# atmega16_generalpurpose_board.net
KiCad netlist of a schematic drawn in EAGLE
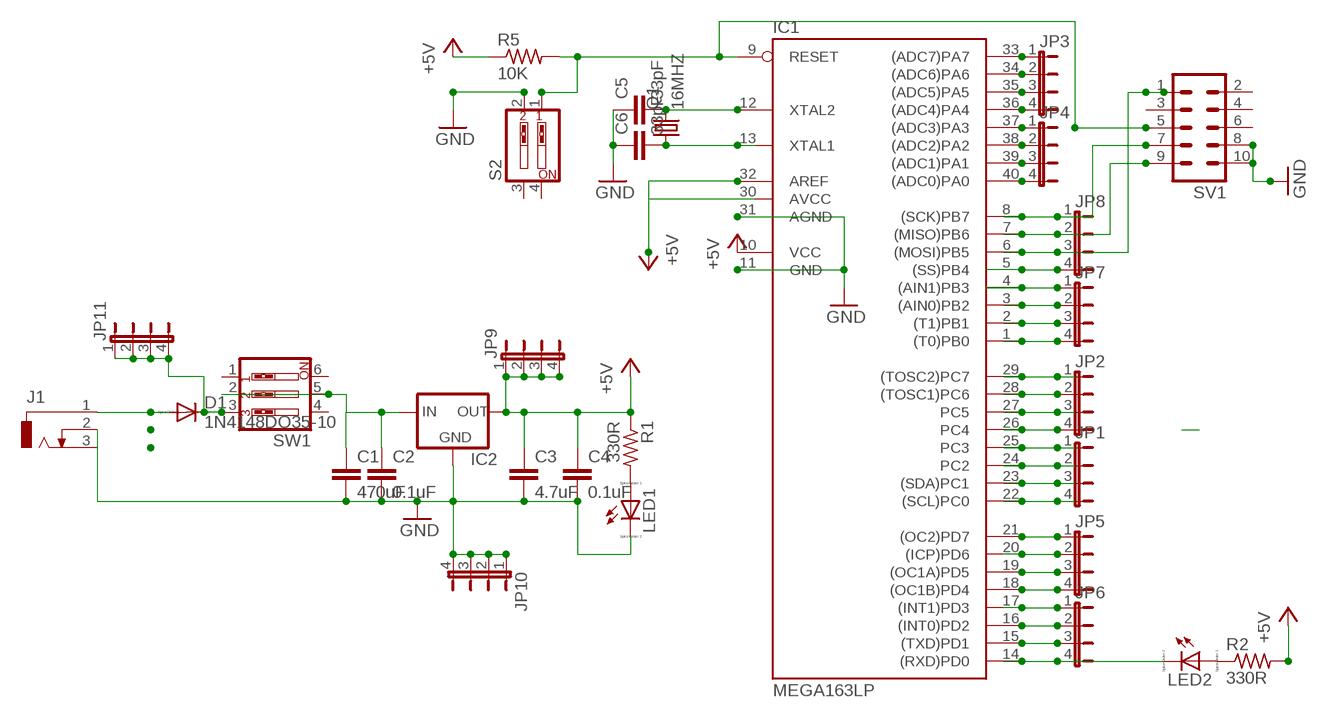
[diagram p0: schematic, sheet 1]

(export (version "E")
  (design (tool "Eeschema 10.0.6"))
  (components
    (comp (ref "C1")
      (value "470uF")
      (footprint "eagle-import:C2.5-4")
      (libsource (lib "eagle-import") (part "C2.5/4"))
    )
    (comp (ref "C2")
      (value "0.1uF")
      (footprint "eagle-import:C2.5-4")
      (libsource (lib "eagle-import") (part "C2.5/4"))
    )
    (comp (ref "C3")
      (value "4.7uF")
      (footprint "eagle-import:C2.5-4")
      (libsource (lib "eagle-import") (part "C2.5/4"))
    )
    (comp (ref "C4")
      (value "0.1uF")
      (footprint "eagle-import:C2.5-4")
      (libsource (lib "eagle-import") (part "C2.5/4"))
    )
    (comp (ref "C5")
      (value "33pF")
      (footprint "eagle-import:C2.5-4")
      (libsource (lib "eagle-import") (part "C2.5/4"))
    )
    (comp (ref "C6")
      (value "33pF")
      (footprint "eagle-import:C2.5-4")
      (libsource (lib "eagle-import") (part "C2.5/4"))
    )
    (comp (ref "D1")
      (value "1N4148DO35-10")
      (footprint "eagle-import:DO35-10")
      (libsource (lib "eagle-import") (part "1N4148DO35-10"))
    )
    (comp (ref "IC1")
      (value "MEGA163LP")
      (footprint "eagle-import:DIL40")
      (libsource (lib "eagle-import") (part "MEGA163PL"))
    )
    (comp (ref "IC2")
      (value "78XXS")
      (footprint "eagle-import:78XXS")
      (libsource (lib "eagle-import") (part "78XXS"))
    )
    (comp (ref "J1")
      (value "DCJ0303")
      (footprint "eagle-import:DCJ0303")
      (libsource (lib "eagle-import") (part "DCJ0303"))
    )
    (comp (ref "JP1")
      (value "JP4E")
      (footprint "eagle-import:JP4")
      (libsource (lib "eagle-import") (part "JP4E"))
    )
    (comp (ref "JP2")
      (value "JP4E")
      (footprint "eagle-import:JP4")
      (libsource (lib "eagle-import") (part "JP4E"))
    )
    (comp (ref "JP3")
      (value "JP4E")
      (footprint "eagle-import:JP4")
      (libsource (lib "eagle-import") (part "JP4E"))
    )
    (comp (ref "JP4")
      (value "JP4E")
      (footprint "eagle-import:JP4")
      (libsource (lib "eagle-import") (part "JP4E"))
    )
    (comp (ref "JP5")
      (value "JP4E")
      (footprint "eagle-import:JP4")
      (libsource (lib "eagle-import") (part "JP4E"))
    )
    (comp (ref "JP6")
      (value "JP4E")
      (footprint "eagle-import:JP4")
      (libsource (lib "eagle-import") (part "JP4E"))
    )
    (comp (ref "JP7")
      (value "JP4E")
      (footprint "eagle-import:JP4")
      (libsource (lib "eagle-import") (part "JP4E"))
    )
    (comp (ref "JP8")
      (value "JP4E")
      (footprint "eagle-import:JP4")
      (libsource (lib "eagle-import") (part "JP4E"))
    )
    (comp (ref "JP9")
      (value "JP4E")
      (footprint "eagle-import:JP4")
      (libsource (lib "eagle-import") (part "JP4E"))
    )
    (comp (ref "JP10")
      (value "JP4E")
      (footprint "eagle-import:JP4")
      (libsource (lib "eagle-import") (part "JP4E"))
    )
    (comp (ref "JP11")
      (value "JP4E")
      (footprint "eagle-import:JP4")
      (libsource (lib "eagle-import") (part "JP4E"))
    )
    (comp (ref "LED1")
      (value "LED_ELD260")
      (footprint "eagle-import:LED_LD260")
      (libsource (lib "eagle-import") (part "LED_ELD260"))
    )
    (comp (ref "LED2")
      (value "LED_ELD260")
      (footprint "eagle-import:LED_LD260")
      (libsource (lib "eagle-import") (part "LED_ELD260"))
    )
    (comp (ref "Q1")
      (value "16MHZ")
      (footprint "eagle-import:HC49U-V")
      (libsource (lib "eagle-import") (part "CRYSTALHC49U-V"))
    )
    (comp (ref "R1")
      (value "330R")
      (footprint "eagle-import:0204_7")
      (libsource (lib "eagle-import") (part "R-US_0204/7"))
    )
    (comp (ref "R2")
      (value "330R")
      (footprint "eagle-import:0204_7")
      (libsource (lib "eagle-import") (part "R-US_0204/7"))
    )
    (comp (ref "R5")
      (value "10K")
      (footprint "eagle-import:0204_7")
      (libsource (lib "eagle-import") (part "R-US_0204/7"))
    )
    (comp (ref "S2")
      (value "SW_DIP-2")
      (footprint "eagle-import:EDG-02")
      (libsource (lib "eagle-import") (part "SW_DIP-2"))
    )
    (comp (ref "SV1")
      (value "MA05-2")
      (footprint "eagle-import:MA05-2")
      (libsource (lib "eagle-import") (part "MA05-2"))
    )
    (comp (ref "SW1")
      (value "SW_DIP-3")
      (footprint "eagle-import:EDG-03")
      (libsource (lib "eagle-import") (part "SW_DIP-3"))
    )
  )
  (nets
    (net (code "1") (name "+5V") (class "Default")
      (node (ref "C3") (pin "1") (pinfunction "1_1") (pintype "passive"))
      (node (ref "C4") (pin "1") (pinfunction "1_1") (pintype "passive"))
      (node (ref "IC1") (pin "10") (pinfunction "VCC_10") (pintype "power_in"))
      (node (ref "IC1") (pin "32") (pinfunction "AREF_32") (pintype "passive"))
      (node (ref "IC2") (pin "OUT") (pinfunction "OUT_OUT") (pintype "passive"))
      (node (ref "JP9") (pin "1") (pinfunction "1_1") (pintype "passive"))
      (node (ref "JP9") (pin "2") (pinfunction "2_2") (pintype "passive"))
      (node (ref "JP9") (pin "3") (pinfunction "3_3") (pintype "passive"))
      (node (ref "JP9") (pin "4") (pinfunction "4_4") (pintype "passive"))
      (node (ref "R1") (pin "1") (pinfunction "1_1") (pintype "passive"))
      (node (ref "R2") (pin "2") (pinfunction "2_2") (pintype "passive"))
      (node (ref "R5") (pin "1") (pinfunction "1_1") (pintype "passive"))
    )
    (net (code "2") (name "/AVCC") (class "Default")
      (node (ref "IC1") (pin "30") (pinfunction "AVCC_30") (pintype "power_in"))
    )
    (net (code "3") (name "/N$18") (class "Default")
      (node (ref "IC1") (pin "27") (pinfunction "PC5_27") (pintype "bidirectional"))
      (node (ref "JP2") (pin "3") (pinfunction "3_3") (pintype "passive"))
    )
    (net (code "4") (name "GND") (class "Default")
      (node (ref "C1") (pin "2") (pinfunction "2_2") (pintype "passive"))
      (node (ref "C2") (pin "2") (pinfunction "2_2") (pintype "passive"))
      (node (ref "C3") (pin "2") (pinfunction "2_2") (pintype "passive"))
      (node (ref "C4") (pin "2") (pinfunction "2_2") (pintype "passive"))
      (node (ref "C5") (pin "1") (pinfunction "1_1") (pintype "passive"))
      (node (ref "C6") (pin "1") (pinfunction "1_1") (pintype "passive"))
      (node (ref "IC1") (pin "11") (pinfunction "GND_11") (pintype "power_in"))
      (node (ref "IC1") (pin "31") (pinfunction "AGND_31") (pintype "power_in"))
      (node (ref "IC2") (pin "GND") (pinfunction "GND_GND") (pintype "input"))
      (node (ref "J1") (pin "2") (pinfunction "2_2") (pintype "passive"))
      (node (ref "J1") (pin "3") (pinfunction "3_3") (pintype "passive"))
      (node (ref "JP10") (pin "1") (pinfunction "1_1") (pintype "passive"))
      (node (ref "JP10") (pin "2") (pinfunction "2_2") (pintype "passive"))
      (node (ref "JP10") (pin "3") (pinfunction "3_3") (pintype "passive"))
      (node (ref "JP10") (pin "4") (pinfunction "4_4") (pintype "passive"))
      (node (ref "LED1") (pin "K") (pinfunction "C_K") (pintype "passive"))
      (node (ref "S2") (pin "2") (pinfunction "2_2") (pintype "passive"))
      (node (ref "SV1") (pin "10") (pinfunction "10_10") (pintype "passive"))
      (node (ref "SV1") (pin "8") (pinfunction "8_8") (pintype "passive"))
    )
    (net (code "5") (name "Net-(C1-Pad1)") (class "Default")
      (node (ref "C1") (pin "1") (pinfunction "1_1") (pintype "passive"))
      (node (ref "C2") (pin "1") (pinfunction "1_1") (pintype "passive"))
      (node (ref "IC2") (pin "IN") (pinfunction "IN_IN") (pintype "input"))
      (node (ref "SW1") (pin "2") (pinfunction "2_2") (pintype "passive"))
      (node (ref "SW1") (pin "5") (pinfunction "5_5") (pintype "passive"))
    )
    (net (code "6") (name "Net-(D1-PadA)") (class "Default")
      (node (ref "D1") (pin "A") (pinfunction "A_A") (pintype "passive"))
      (node (ref "J1") (pin "1") (pinfunction "1_1") (pintype "passive"))
    )
    (net (code "7") (name "Net-(D1-PadC)") (class "Default")
      (node (ref "D1") (pin "C") (pinfunction "C_C") (pintype "passive"))
      (node (ref "JP11") (pin "1") (pinfunction "1_1") (pintype "passive"))
      (node (ref "JP11") (pin "2") (pinfunction "2_2") (pintype "passive"))
      (node (ref "JP11") (pin "3") (pinfunction "3_3") (pintype "passive"))
      (node (ref "JP11") (pin "4") (pinfunction "4_4") (pintype "passive"))
      (node (ref "SW1") (pin "3") (pinfunction "3_3") (pintype "passive"))
    )
    (net (code "8") (name "Net-(IC1-(ADC0)PA0)") (class "Default")
      (node (ref "IC1") (pin "40") (pinfunction "(ADC0)PA0_40") (pintype "bidirectional"))
      (node (ref "JP4") (pin "4") (pinfunction "4_4") (pintype "passive"))
    )
    (net (code "9") (name "Net-(IC1-(ADC1)PA1)") (class "Default")
      (node (ref "IC1") (pin "39") (pinfunction "(ADC1)PA1_39") (pintype "bidirectional"))
      (node (ref "JP4") (pin "3") (pinfunction "3_3") (pintype "passive"))
    )
    (net (code "10") (name "Net-(IC1-(ADC2)PA2)") (class "Default")
      (node (ref "IC1") (pin "38") (pinfunction "(ADC2)PA2_38") (pintype "bidirectional"))
      (node (ref "JP4") (pin "2") (pinfunction "2_2") (pintype "passive"))
    )
    (net (code "11") (name "Net-(IC1-(ADC3)PA3)") (class "Default")
      (node (ref "IC1") (pin "37") (pinfunction "(ADC3)PA3_37") (pintype "bidirectional"))
      (node (ref "JP4") (pin "1") (pinfunction "1_1") (pintype "passive"))
    )
    (net (code "12") (name "Net-(IC1-(ADC4)PA4)") (class "Default")
      (node (ref "IC1") (pin "36") (pinfunction "(ADC4)PA4_36") (pintype "bidirectional"))
      (node (ref "JP3") (pin "4") (pinfunction "4_4") (pintype "passive"))
    )
    (net (code "13") (name "Net-(IC1-(ADC5)PA5)") (class "Default")
      (node (ref "IC1") (pin "35") (pinfunction "(ADC5)PA5_35") (pintype "bidirectional"))
      (node (ref "JP3") (pin "3") (pinfunction "3_3") (pintype "passive"))
    )
    (net (code "14") (name "Net-(IC1-(ADC6)PA6)") (class "Default")
      (node (ref "IC1") (pin "34") (pinfunction "(ADC6)PA6_34") (pintype "bidirectional"))
      (node (ref "JP3") (pin "2") (pinfunction "2_2") (pintype "passive"))
    )
    (net (code "15") (name "Net-(IC1-(ADC7)PA7)") (class "Default")
      (node (ref "IC1") (pin "33") (pinfunction "(ADC7)PA7_33") (pintype "bidirectional"))
      (node (ref "JP3") (pin "1") (pinfunction "1_1") (pintype "passive"))
    )
    (net (code "16") (name "Net-(IC1-(AIN0)PB2)") (class "Default")
      (node (ref "IC1") (pin "3") (pinfunction "(AIN0)PB2_3") (pintype "bidirectional"))
      (node (ref "JP7") (pin "2") (pinfunction "2_2") (pintype "passive"))
    )
    (net (code "17") (name "Net-(IC1-(AIN1)PB3)") (class "Default")
      (node (ref "IC1") (pin "4") (pinfunction "(AIN1)PB3_4") (pintype "bidirectional"))
      (node (ref "JP7") (pin "1") (pinfunction "1_1") (pintype "passive"))
    )
    (net (code "18") (name "Net-(IC1-(ICP)PD6)") (class "Default")
      (node (ref "IC1") (pin "20") (pinfunction "(ICP)PD6_20") (pintype "bidirectional"))
      (node (ref "JP5") (pin "2") (pinfunction "2_2") (pintype "passive"))
    )
    (net (code "19") (name "Net-(IC1-(INT0)PD2)") (class "Default")
      (node (ref "IC1") (pin "16") (pinfunction "(INT0)PD2_16") (pintype "bidirectional"))
      (node (ref "JP6") (pin "2") (pinfunction "2_2") (pintype "passive"))
    )
    (net (code "20") (name "Net-(IC1-(INT1)PD3)") (class "Default")
      (node (ref "IC1") (pin "17") (pinfunction "(INT1)PD3_17") (pintype "bidirectional"))
      (node (ref "JP6") (pin "1") (pinfunction "1_1") (pintype "passive"))
    )
    (net (code "21") (name "Net-(IC1-(MISO)PB6)") (class "Default")
      (node (ref "IC1") (pin "7") (pinfunction "(MISO)PB6_7") (pintype "bidirectional"))
      (node (ref "JP8") (pin "2") (pinfunction "2_2") (pintype "passive"))
      (node (ref "SV1") (pin "9") (pinfunction "9_9") (pintype "passive"))
    )
    (net (code "22") (name "Net-(IC1-(MOSI)PB5)") (class "Default")
      (node (ref "IC1") (pin "6") (pinfunction "(MOSI)PB5_6") (pintype "bidirectional"))
      (node (ref "JP8") (pin "3") (pinfunction "3_3") (pintype "passive"))
      (node (ref "SV1") (pin "1") (pinfunction "1_1") (pintype "passive"))
    )
    (net (code "23") (name "Net-(IC1-(OC1A)PD5)") (class "Default")
      (node (ref "IC1") (pin "19") (pinfunction "(OC1A)PD5_19") (pintype "bidirectional"))
      (node (ref "JP5") (pin "3") (pinfunction "3_3") (pintype "passive"))
    )
    (net (code "24") (name "Net-(IC1-(OC1B)PD4)") (class "Default")
      (node (ref "IC1") (pin "18") (pinfunction "(OC1B)PD4_18") (pintype "bidirectional"))
      (node (ref "JP5") (pin "4") (pinfunction "4_4") (pintype "passive"))
    )
    (net (code "25") (name "Net-(IC1-(OC2)PD7)") (class "Default")
      (node (ref "IC1") (pin "21") (pinfunction "(OC2)PD7_21") (pintype "bidirectional"))
      (node (ref "JP5") (pin "1") (pinfunction "1_1") (pintype "passive"))
    )
    (net (code "26") (name "Net-(IC1-(RXD)PD0)") (class "Default")
      (node (ref "IC1") (pin "14") (pinfunction "(RXD)PD0_14") (pintype "bidirectional"))
      (node (ref "JP6") (pin "4") (pinfunction "4_4") (pintype "passive"))
      (node (ref "LED2") (pin "K") (pinfunction "C_K") (pintype "passive"))
    )
    (net (code "27") (name "Net-(IC1-(SCK)PB7)") (class "Default")
      (node (ref "IC1") (pin "8") (pinfunction "(SCK)PB7_8") (pintype "bidirectional"))
      (node (ref "JP8") (pin "1") (pinfunction "1_1") (pintype "passive"))
      (node (ref "SV1") (pin "7") (pinfunction "7_7") (pintype "passive"))
    )
    (net (code "28") (name "Net-(IC1-(SCL)PC0)") (class "Default")
      (node (ref "IC1") (pin "22") (pinfunction "(SCL)PC0_22") (pintype "bidirectional"))
      (node (ref "JP1") (pin "4") (pinfunction "4_4") (pintype "passive"))
    )
    (net (code "29") (name "Net-(IC1-(SDA)PC1)") (class "Default")
      (node (ref "IC1") (pin "23") (pinfunction "(SDA)PC1_23") (pintype "bidirectional"))
      (node (ref "JP1") (pin "3") (pinfunction "3_3") (pintype "passive"))
    )
    (net (code "30") (name "Net-(IC1-(SS)PB4)") (class "Default")
      (node (ref "IC1") (pin "5") (pinfunction "(SS)PB4_5") (pintype "bidirectional"))
      (node (ref "JP8") (pin "4") (pinfunction "4_4") (pintype "passive"))
    )
    (net (code "31") (name "Net-(IC1-(T0)PB0)") (class "Default")
      (node (ref "IC1") (pin "1") (pinfunction "(T0)PB0_1") (pintype "bidirectional"))
      (node (ref "JP7") (pin "4") (pinfunction "4_4") (pintype "passive"))
    )
    (net (code "32") (name "Net-(IC1-(T1)PB1)") (class "Default")
      (node (ref "IC1") (pin "2") (pinfunction "(T1)PB1_2") (pintype "bidirectional"))
      (node (ref "JP7") (pin "3") (pinfunction "3_3") (pintype "passive"))
    )
    (net (code "33") (name "Net-(IC1-(TOSC1)PC6)") (class "Default")
      (node (ref "IC1") (pin "28") (pinfunction "(TOSC1)PC6_28") (pintype "bidirectional"))
      (node (ref "JP2") (pin "2") (pinfunction "2_2") (pintype "passive"))
    )
    (net (code "34") (name "Net-(IC1-(TOSC2)PC7)") (class "Default")
      (node (ref "IC1") (pin "29") (pinfunction "(TOSC2)PC7_29") (pintype "bidirectional"))
      (node (ref "JP2") (pin "1") (pinfunction "1_1") (pintype "passive"))
    )
    (net (code "35") (name "Net-(IC1-(TXD)PD1)") (class "Default")
      (node (ref "IC1") (pin "15") (pinfunction "(TXD)PD1_15") (pintype "bidirectional"))
      (node (ref "JP6") (pin "3") (pinfunction "3_3") (pintype "passive"))
    )
    (net (code "36") (name "Net-(IC1-PC2)") (class "Default")
      (node (ref "IC1") (pin "24") (pinfunction "PC2_24") (pintype "bidirectional"))
      (node (ref "JP1") (pin "2") (pinfunction "2_2") (pintype "passive"))
    )
    (net (code "37") (name "Net-(IC1-PC3)") (class "Default")
      (node (ref "IC1") (pin "25") (pinfunction "PC3_25") (pintype "bidirectional"))
      (node (ref "JP1") (pin "1") (pinfunction "1_1") (pintype "passive"))
    )
    (net (code "38") (name "Net-(IC1-PC4)") (class "Default")
      (node (ref "IC1") (pin "26") (pinfunction "PC4_26") (pintype "bidirectional"))
      (node (ref "JP2") (pin "4") (pinfunction "4_4") (pintype "passive"))
    )
    (net (code "39") (name "Net-(IC1-RESET)") (class "Default")
      (node (ref "IC1") (pin "9") (pinfunction "RESET_9") (pintype "input"))
      (node (ref "R5") (pin "2") (pinfunction "2_2") (pintype "passive"))
      (node (ref "S2") (pin "1") (pinfunction "1_1") (pintype "passive"))
      (node (ref "SV1") (pin "5") (pinfunction "5_5") (pintype "passive"))
    )
    (net (code "40") (name "Net-(IC1-XTAL1)") (class "Default")
      (node (ref "C6") (pin "2") (pinfunction "2_2") (pintype "passive"))
      (node (ref "IC1") (pin "13") (pinfunction "XTAL1_13") (pintype "bidirectional"))
      (node (ref "Q1") (pin "1") (pinfunction "1_1") (pintype "passive"))
    )
    (net (code "41") (name "Net-(IC1-XTAL2)") (class "Default")
      (node (ref "C5") (pin "2") (pinfunction "2_2") (pintype "passive"))
      (node (ref "IC1") (pin "12") (pinfunction "XTAL2_12") (pintype "bidirectional"))
      (node (ref "Q1") (pin "2") (pinfunction "2_2") (pintype "passive"))
    )
    (net (code "42") (name "Net-(LED1-PadA)") (class "Default")
      (node (ref "LED1") (pin "A") (pinfunction "A_A") (pintype "passive"))
      (node (ref "R1") (pin "2") (pinfunction "2_2") (pintype "passive"))
    )
    (net (code "43") (name "Net-(LED2-PadA)") (class "Default")
      (node (ref "LED2") (pin "A") (pinfunction "A_A") (pintype "passive"))
      (node (ref "R2") (pin "1") (pinfunction "1_1") (pintype "passive"))
    )
    (net (code "44") (name "unconnected-(S2-Pad3)") (class "Default")
      (node (ref "S2") (pin "3") (pinfunction "3_3") (pintype "passive"))
    )
    (net (code "45") (name "unconnected-(S2-Pad4)") (class "Default")
      (node (ref "S2") (pin "4") (pinfunction "4_4") (pintype "passive"))
    )
    (net (code "46") (name "unconnected-(SV1-Pad2)") (class "Default")
      (node (ref "SV1") (pin "2") (pinfunction "2_2") (pintype "passive"))
    )
    (net (code "47") (name "unconnected-(SV1-Pad3)") (class "Default")
      (node (ref "SV1") (pin "3") (pinfunction "3_3") (pintype "passive"))
    )
    (net (code "48") (name "unconnected-(SV1-Pad4)") (class "Default")
      (node (ref "SV1") (pin "4") (pinfunction "4_4") (pintype "passive"))
    )
    (net (code "49") (name "unconnected-(SV1-Pad6)") (class "Default")
      (node (ref "SV1") (pin "6") (pinfunction "6_6") (pintype "passive"))
    )
    (net (code "50") (name "unconnected-(SW1-Pad1)") (class "Default")
      (node (ref "SW1") (pin "1") (pinfunction "1_1") (pintype "passive"))
    )
    (net (code "51") (name "unconnected-(SW1-Pad4)") (class "Default")
      (node (ref "SW1") (pin "4") (pinfunction "4_4") (pintype "passive"))
    )
    (net (code "52") (name "unconnected-(SW1-Pad6)") (class "Default")
      (node (ref "SW1") (pin "6") (pinfunction "6_6") (pintype "passive"))
    )
  )
)
